# xmos1.net
KiCad netlist of a schematic drawn in EAGLE
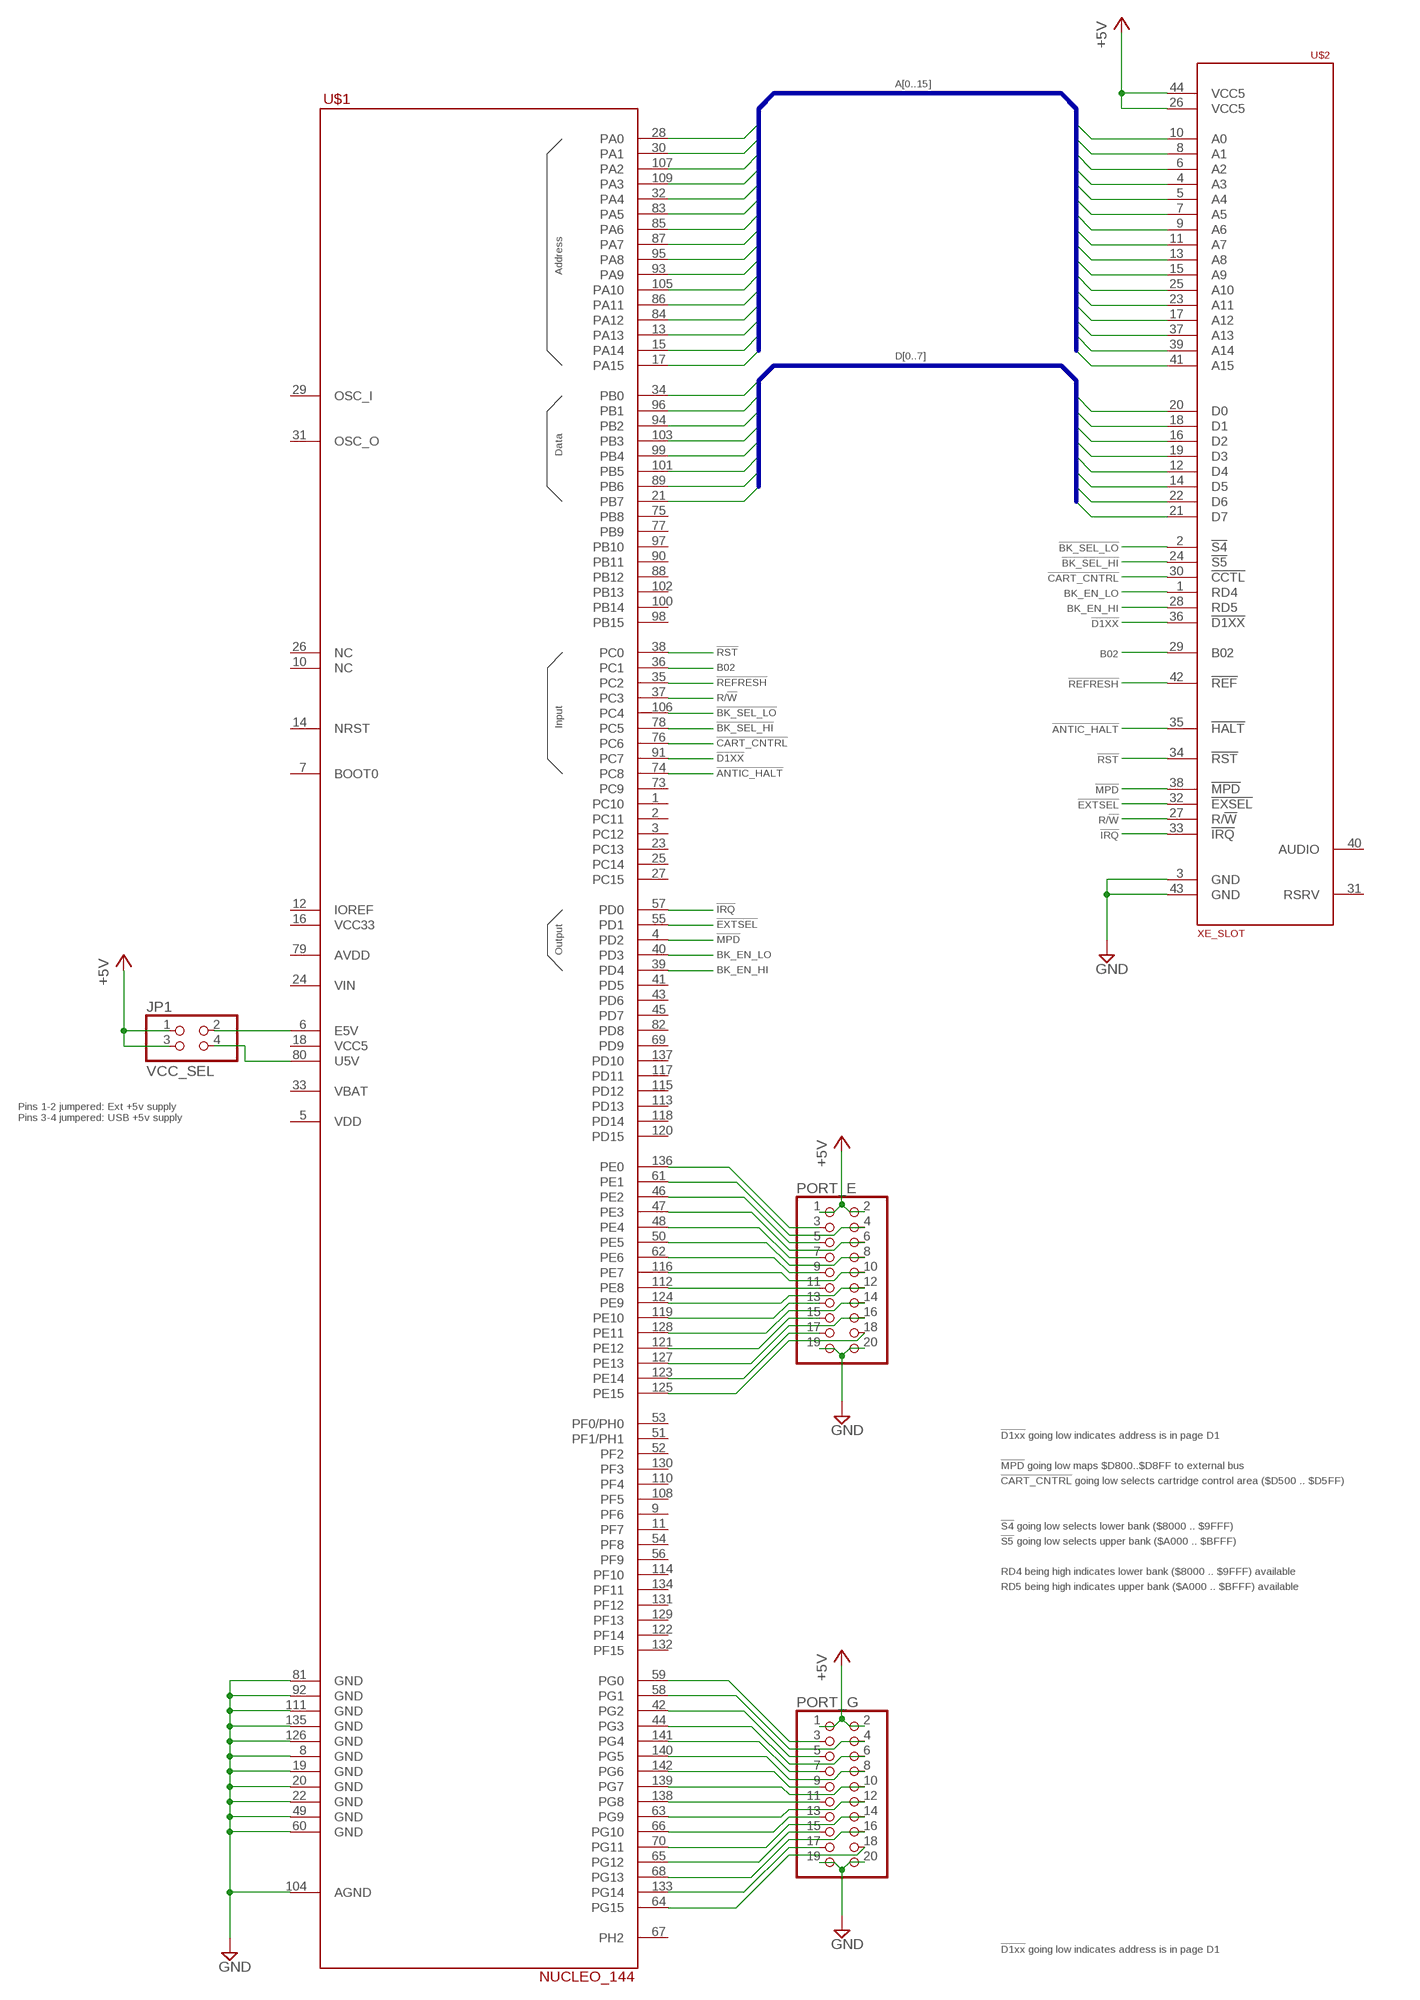
[diagram p0: schematic, sheet 1]

(export (version "E")
  (design (tool "Eeschema 10.0.6"))
  (components
    (comp (ref "JP1")
      (value "VCC_SEL")
      (footprint "eagle-import:2X02")
      (libsource (lib "eagle-import") (part "PINHD-2X2"))
    )
    (comp (ref "PORT_E")
      (value "PINHD-2X10")
      (footprint "eagle-import:2X10")
      (libsource (lib "eagle-import") (part "PINHD-2X10"))
    )
    (comp (ref "PORT_G")
      (value "PINHD-2X10")
      (footprint "eagle-import:2X10")
      (libsource (lib "eagle-import") (part "PINHD-2X10"))
    )
    (comp (ref "U$1")
      (value "NUCLEO_144")
      (footprint "eagle-import:NUCLEO_144")
      (libsource (lib "eagle-import") (part "NUCLEO_144"))
    )
    (comp (ref "U$2")
      (value "XE_SLOT")
      (footprint "eagle-import:XE_SLOT")
      (libsource (lib "eagle-import") (part "XE_SLOT"))
    )
  )
  (nets
    (net (code "1") (name "+5V") (class "Default")
      (node (ref "JP1") (pin "1") (pinfunction "1_1") (pintype "passive"))
      (node (ref "JP1") (pin "3") (pinfunction "3_3") (pintype "passive"))
      (node (ref "PORT_E") (pin "1") (pinfunction "1_1") (pintype "passive"))
      (node (ref "PORT_E") (pin "2") (pinfunction "2_2") (pintype "passive"))
      (node (ref "PORT_G") (pin "1") (pinfunction "1_1") (pintype "passive"))
      (node (ref "PORT_G") (pin "2") (pinfunction "2_2") (pintype "passive"))
      (node (ref "U$2") (pin "26") (pinfunction "VCC5_26") (pintype "bidirectional"))
      (node (ref "U$2") (pin "44") (pinfunction "VCC5_44") (pintype "bidirectional"))
    )
    (net (code "2") (name "/A0") (class "Default")
      (node (ref "U$1") (pin "28") (pinfunction "PA0_28") (pintype "bidirectional"))
      (node (ref "U$2") (pin "10") (pinfunction "A0_10") (pintype "bidirectional"))
    )
    (net (code "3") (name "/A1") (class "Default")
      (node (ref "U$1") (pin "30") (pinfunction "PA1_30") (pintype "bidirectional"))
      (node (ref "U$2") (pin "8") (pinfunction "A1_8") (pintype "bidirectional"))
    )
    (net (code "4") (name "/A2") (class "Default")
      (node (ref "U$1") (pin "107") (pinfunction "PA2_107") (pintype "bidirectional"))
      (node (ref "U$2") (pin "6") (pinfunction "A2_6") (pintype "bidirectional"))
    )
    (net (code "5") (name "/A3") (class "Default")
      (node (ref "U$1") (pin "109") (pinfunction "PA3_109") (pintype "bidirectional"))
      (node (ref "U$2") (pin "4") (pinfunction "A3_4") (pintype "bidirectional"))
    )
    (net (code "6") (name "/A4") (class "Default")
      (node (ref "U$1") (pin "32") (pinfunction "PA4_32") (pintype "bidirectional"))
      (node (ref "U$2") (pin "5") (pinfunction "A4_5") (pintype "bidirectional"))
    )
    (net (code "7") (name "/A5") (class "Default")
      (node (ref "U$1") (pin "83") (pinfunction "PA5_83") (pintype "bidirectional"))
      (node (ref "U$2") (pin "7") (pinfunction "A5_7") (pintype "bidirectional"))
    )
    (net (code "8") (name "/A6") (class "Default")
      (node (ref "U$1") (pin "85") (pinfunction "PA6_85") (pintype "bidirectional"))
      (node (ref "U$2") (pin "9") (pinfunction "A6_9") (pintype "bidirectional"))
    )
    (net (code "9") (name "/A7") (class "Default")
      (node (ref "U$1") (pin "87") (pinfunction "PA7_87") (pintype "bidirectional"))
      (node (ref "U$2") (pin "11") (pinfunction "A7_11") (pintype "bidirectional"))
    )
    (net (code "10") (name "/A8") (class "Default")
      (node (ref "U$1") (pin "95") (pinfunction "PA8_95") (pintype "bidirectional"))
      (node (ref "U$2") (pin "13") (pinfunction "A8_13") (pintype "bidirectional"))
    )
    (net (code "11") (name "/A9") (class "Default")
      (node (ref "U$1") (pin "93") (pinfunction "PA9_93") (pintype "bidirectional"))
      (node (ref "U$2") (pin "15") (pinfunction "A9_15") (pintype "bidirectional"))
    )
    (net (code "12") (name "/A10") (class "Default")
      (node (ref "U$1") (pin "105") (pinfunction "PA10_105") (pintype "bidirectional"))
      (node (ref "U$2") (pin "25") (pinfunction "A10_25") (pintype "bidirectional"))
    )
    (net (code "13") (name "/A11") (class "Default")
      (node (ref "U$1") (pin "86") (pinfunction "PA11_86") (pintype "bidirectional"))
      (node (ref "U$2") (pin "23") (pinfunction "A11_23") (pintype "bidirectional"))
    )
    (net (code "14") (name "/A12") (class "Default")
      (node (ref "U$1") (pin "84") (pinfunction "PA12_84") (pintype "bidirectional"))
      (node (ref "U$2") (pin "17") (pinfunction "A12_17") (pintype "bidirectional"))
    )
    (net (code "15") (name "/A13") (class "Default")
      (node (ref "U$1") (pin "13") (pinfunction "PA13_13") (pintype "bidirectional"))
      (node (ref "U$2") (pin "37") (pinfunction "A13_37") (pintype "bidirectional"))
    )
    (net (code "16") (name "/A14") (class "Default")
      (node (ref "U$1") (pin "15") (pinfunction "PA14_15") (pintype "bidirectional"))
      (node (ref "U$2") (pin "39") (pinfunction "A14_39") (pintype "bidirectional"))
    )
    (net (code "17") (name "/A15") (class "Default")
      (node (ref "U$1") (pin "17") (pinfunction "PA15_17") (pintype "bidirectional"))
      (node (ref "U$2") (pin "41") (pinfunction "A15_41") (pintype "bidirectional"))
    )
    (net (code "19") (name "/B02") (class "Default")
      (node (ref "U$1") (pin "36") (pinfunction "PC1_36") (pintype "bidirectional"))
      (node (ref "U$2") (pin "29") (pinfunction "B02_29") (pintype "bidirectional"))
    )
    (net (code "20") (name "/BK_EN_HI") (class "Default")
      (node (ref "U$1") (pin "39") (pinfunction "PD4_39") (pintype "bidirectional"))
      (node (ref "U$2") (pin "28") (pinfunction "RD5_28") (pintype "bidirectional"))
    )
    (net (code "21") (name "/BK_EN_LO") (class "Default")
      (node (ref "U$1") (pin "40") (pinfunction "PD3_40") (pintype "bidirectional"))
      (node (ref "U$2") (pin "1") (pinfunction "RD4_1") (pintype "bidirectional"))
    )
    (net (code "22") (name "/D0") (class "Default")
      (node (ref "U$1") (pin "34") (pinfunction "PB0_34") (pintype "bidirectional"))
      (node (ref "U$2") (pin "20") (pinfunction "D0_20") (pintype "bidirectional"))
    )
    (net (code "23") (name "/D1") (class "Default")
      (node (ref "U$1") (pin "96") (pinfunction "PB1_96") (pintype "bidirectional"))
      (node (ref "U$2") (pin "18") (pinfunction "D1_18") (pintype "bidirectional"))
    )
    (net (code "24") (name "/D2") (class "Default")
      (node (ref "U$1") (pin "94") (pinfunction "PB2_94") (pintype "bidirectional"))
      (node (ref "U$2") (pin "16") (pinfunction "D2_16") (pintype "bidirectional"))
    )
    (net (code "25") (name "/D3") (class "Default")
      (node (ref "U$1") (pin "103") (pinfunction "PB3_103") (pintype "bidirectional"))
      (node (ref "U$2") (pin "19") (pinfunction "D3_19") (pintype "bidirectional"))
    )
    (net (code "26") (name "/D4") (class "Default")
      (node (ref "U$1") (pin "99") (pinfunction "PB4_99") (pintype "bidirectional"))
      (node (ref "U$2") (pin "12") (pinfunction "D4_12") (pintype "bidirectional"))
    )
    (net (code "27") (name "/D5") (class "Default")
      (node (ref "U$1") (pin "101") (pinfunction "PB5_101") (pintype "bidirectional"))
      (node (ref "U$2") (pin "14") (pinfunction "D5_14") (pintype "bidirectional"))
    )
    (net (code "28") (name "/D6") (class "Default")
      (node (ref "U$1") (pin "89") (pinfunction "PB6_89") (pintype "bidirectional"))
      (node (ref "U$2") (pin "22") (pinfunction "D6_22") (pintype "bidirectional"))
    )
    (net (code "29") (name "/D7") (class "Default")
      (node (ref "U$1") (pin "21") (pinfunction "PB7_21") (pintype "bidirectional"))
      (node (ref "U$2") (pin "21") (pinfunction "D7_21") (pintype "bidirectional"))
    )
    (net (code "31") (name "/R{slash}~{W}") (class "Default")
      (node (ref "U$1") (pin "37") (pinfunction "PC3_37") (pintype "bidirectional"))
      (node (ref "U$2") (pin "27") (pinfunction "R/~{W}_27") (pintype "bidirectional"))
    )
    (net (code "32") (name "/~{ANTIC_HALT}") (class "Default")
      (node (ref "U$1") (pin "74") (pinfunction "PC8_74") (pintype "bidirectional"))
      (node (ref "U$2") (pin "35") (pinfunction "~{HALT}_35") (pintype "bidirectional"))
    )
    (net (code "33") (name "/~{BK_SEL_HI}") (class "Default")
      (node (ref "U$1") (pin "78") (pinfunction "PC5_78") (pintype "bidirectional"))
      (node (ref "U$2") (pin "24") (pinfunction "~{S5}_24") (pintype "bidirectional"))
    )
    (net (code "34") (name "/~{BK_SEL_LO}") (class "Default")
      (node (ref "U$1") (pin "106") (pinfunction "PC4_106") (pintype "bidirectional"))
      (node (ref "U$2") (pin "2") (pinfunction "~{S4}_2") (pintype "bidirectional"))
    )
    (net (code "35") (name "/~{CART_CNTRL}") (class "Default")
      (node (ref "U$1") (pin "76") (pinfunction "PC6_76") (pintype "bidirectional"))
      (node (ref "U$2") (pin "30") (pinfunction "~{CCTL}_30") (pintype "bidirectional"))
    )
    (net (code "36") (name "/~{D1XX}") (class "Default")
      (node (ref "U$1") (pin "91") (pinfunction "PC7_91") (pintype "bidirectional"))
      (node (ref "U$2") (pin "36") (pinfunction "~{D1XX}_36") (pintype "bidirectional"))
    )
    (net (code "37") (name "/~{EXTSEL}") (class "Default")
      (node (ref "U$1") (pin "55") (pinfunction "PD1_55") (pintype "bidirectional"))
      (node (ref "U$2") (pin "32") (pinfunction "~{EXSEL}_32") (pintype "bidirectional"))
    )
    (net (code "38") (name "/~{IRQ}") (class "Default")
      (node (ref "U$1") (pin "57") (pinfunction "PD0_57") (pintype "bidirectional"))
      (node (ref "U$2") (pin "33") (pinfunction "~{IRQ}_33") (pintype "bidirectional"))
    )
    (net (code "39") (name "/~{MPD}") (class "Default")
      (node (ref "U$1") (pin "4") (pinfunction "PD2_4") (pintype "bidirectional"))
      (node (ref "U$2") (pin "38") (pinfunction "~{MPD}_38") (pintype "bidirectional"))
    )
    (net (code "40") (name "/~{REFRESH}") (class "Default")
      (node (ref "U$1") (pin "35") (pinfunction "PC2_35") (pintype "bidirectional"))
      (node (ref "U$2") (pin "42") (pinfunction "~{REF}_42") (pintype "bidirectional"))
    )
    (net (code "41") (name "/~{RST}") (class "Default")
      (node (ref "U$1") (pin "38") (pinfunction "PC0_38") (pintype "bidirectional"))
      (node (ref "U$2") (pin "34") (pinfunction "~{RST}_34") (pintype "bidirectional"))
    )
    (net (code "42") (name "GND") (class "Default")
      (node (ref "PORT_E") (pin "19") (pinfunction "19_19") (pintype "passive"))
      (node (ref "PORT_E") (pin "20") (pinfunction "20_20") (pintype "passive"))
      (node (ref "PORT_G") (pin "19") (pinfunction "19_19") (pintype "passive"))
      (node (ref "PORT_G") (pin "20") (pinfunction "20_20") (pintype "passive"))
      (node (ref "U$1") (pin "104") (pinfunction "AGND_104") (pintype "bidirectional"))
      (node (ref "U$1") (pin "111") (pinfunction "GND_111") (pintype "bidirectional"))
      (node (ref "U$1") (pin "126") (pinfunction "GND_126") (pintype "bidirectional"))
      (node (ref "U$1") (pin "135") (pinfunction "GND_135") (pintype "bidirectional"))
      (node (ref "U$1") (pin "19") (pinfunction "GND_19") (pintype "bidirectional"))
      (node (ref "U$1") (pin "20") (pinfunction "GND_20") (pintype "bidirectional"))
      (node (ref "U$1") (pin "22") (pinfunction "GND_22") (pintype "bidirectional"))
      (node (ref "U$1") (pin "49") (pinfunction "GND_49") (pintype "bidirectional"))
      (node (ref "U$1") (pin "60") (pinfunction "GND_60") (pintype "bidirectional"))
      (node (ref "U$1") (pin "8") (pinfunction "GND_8") (pintype "bidirectional"))
      (node (ref "U$1") (pin "81") (pinfunction "GND_81") (pintype "bidirectional"))
      (node (ref "U$1") (pin "92") (pinfunction "GND_92") (pintype "bidirectional"))
      (node (ref "U$2") (pin "3") (pinfunction "GND_3") (pintype "bidirectional"))
      (node (ref "U$2") (pin "43") (pinfunction "GND_43") (pintype "bidirectional"))
    )
    (net (code "43") (name "Net-(U$1-E5V)") (class "Default")
      (node (ref "JP1") (pin "2") (pinfunction "2_2") (pintype "passive"))
      (node (ref "U$1") (pin "6") (pinfunction "E5V_6") (pintype "bidirectional"))
    )
    (net (code "44") (name "Net-(U$1-PE0)") (class "Default")
      (node (ref "PORT_E") (pin "3") (pinfunction "3_3") (pintype "passive"))
      (node (ref "U$1") (pin "136") (pinfunction "PE0_136") (pintype "bidirectional"))
    )
    (net (code "45") (name "Net-(U$1-PE1)") (class "Default")
      (node (ref "PORT_E") (pin "4") (pinfunction "4_4") (pintype "passive"))
      (node (ref "U$1") (pin "61") (pinfunction "PE1_61") (pintype "bidirectional"))
    )
    (net (code "46") (name "Net-(U$1-PE2)") (class "Default")
      (node (ref "PORT_E") (pin "5") (pinfunction "5_5") (pintype "passive"))
      (node (ref "U$1") (pin "46") (pinfunction "PE2_46") (pintype "bidirectional"))
    )
    (net (code "47") (name "Net-(U$1-PE3)") (class "Default")
      (node (ref "PORT_E") (pin "6") (pinfunction "6_6") (pintype "passive"))
      (node (ref "U$1") (pin "47") (pinfunction "PE3_47") (pintype "bidirectional"))
    )
    (net (code "48") (name "Net-(U$1-PE4)") (class "Default")
      (node (ref "PORT_E") (pin "7") (pinfunction "7_7") (pintype "passive"))
      (node (ref "U$1") (pin "48") (pinfunction "PE4_48") (pintype "bidirectional"))
    )
    (net (code "49") (name "Net-(U$1-PE5)") (class "Default")
      (node (ref "PORT_E") (pin "8") (pinfunction "8_8") (pintype "passive"))
      (node (ref "U$1") (pin "50") (pinfunction "PE5_50") (pintype "bidirectional"))
    )
    (net (code "50") (name "Net-(U$1-PE6)") (class "Default")
      (node (ref "PORT_E") (pin "9") (pinfunction "9_9") (pintype "passive"))
      (node (ref "U$1") (pin "62") (pinfunction "PE6_62") (pintype "bidirectional"))
    )
    (net (code "51") (name "Net-(U$1-PE7)") (class "Default")
      (node (ref "PORT_E") (pin "10") (pinfunction "10_10") (pintype "passive"))
      (node (ref "U$1") (pin "116") (pinfunction "PE7_116") (pintype "bidirectional"))
    )
    (net (code "52") (name "Net-(U$1-PE8)") (class "Default")
      (node (ref "PORT_E") (pin "11") (pinfunction "11_11") (pintype "passive"))
      (node (ref "U$1") (pin "112") (pinfunction "PE8_112") (pintype "bidirectional"))
    )
    (net (code "53") (name "Net-(U$1-PE9)") (class "Default")
      (node (ref "PORT_E") (pin "12") (pinfunction "12_12") (pintype "passive"))
      (node (ref "U$1") (pin "124") (pinfunction "PE9_124") (pintype "bidirectional"))
    )
    (net (code "54") (name "Net-(U$1-PE10)") (class "Default")
      (node (ref "PORT_E") (pin "13") (pinfunction "13_13") (pintype "passive"))
      (node (ref "U$1") (pin "119") (pinfunction "PE10_119") (pintype "bidirectional"))
    )
    (net (code "55") (name "Net-(U$1-PE11)") (class "Default")
      (node (ref "PORT_E") (pin "14") (pinfunction "14_14") (pintype "passive"))
      (node (ref "U$1") (pin "128") (pinfunction "PE11_128") (pintype "bidirectional"))
    )
    (net (code "56") (name "Net-(U$1-PE12)") (class "Default")
      (node (ref "PORT_E") (pin "15") (pinfunction "15_15") (pintype "passive"))
      (node (ref "U$1") (pin "121") (pinfunction "PE12_121") (pintype "bidirectional"))
    )
    (net (code "57") (name "Net-(U$1-PE13)") (class "Default")
      (node (ref "PORT_E") (pin "16") (pinfunction "16_16") (pintype "passive"))
      (node (ref "U$1") (pin "127") (pinfunction "PE13_127") (pintype "bidirectional"))
    )
    (net (code "58") (name "Net-(U$1-PE14)") (class "Default")
      (node (ref "PORT_E") (pin "17") (pinfunction "17_17") (pintype "passive"))
      (node (ref "U$1") (pin "123") (pinfunction "PE14_123") (pintype "bidirectional"))
    )
    (net (code "59") (name "Net-(U$1-PE15)") (class "Default")
      (node (ref "PORT_E") (pin "18") (pinfunction "18_18") (pintype "passive"))
      (node (ref "U$1") (pin "125") (pinfunction "PE15_125") (pintype "bidirectional"))
    )
    (net (code "60") (name "Net-(U$1-PG0)") (class "Default")
      (node (ref "PORT_G") (pin "3") (pinfunction "3_3") (pintype "passive"))
      (node (ref "U$1") (pin "59") (pinfunction "PG0_59") (pintype "bidirectional"))
    )
    (net (code "61") (name "Net-(U$1-PG1)") (class "Default")
      (node (ref "PORT_G") (pin "4") (pinfunction "4_4") (pintype "passive"))
      (node (ref "U$1") (pin "58") (pinfunction "PG1_58") (pintype "bidirectional"))
    )
    (net (code "62") (name "Net-(U$1-PG2)") (class "Default")
      (node (ref "PORT_G") (pin "5") (pinfunction "5_5") (pintype "passive"))
      (node (ref "U$1") (pin "42") (pinfunction "PG2_42") (pintype "bidirectional"))
    )
    (net (code "63") (name "Net-(U$1-PG3)") (class "Default")
      (node (ref "PORT_G") (pin "6") (pinfunction "6_6") (pintype "passive"))
      (node (ref "U$1") (pin "44") (pinfunction "PG3_44") (pintype "bidirectional"))
    )
    (net (code "64") (name "Net-(U$1-PG4)") (class "Default")
      (node (ref "PORT_G") (pin "7") (pinfunction "7_7") (pintype "passive"))
      (node (ref "U$1") (pin "141") (pinfunction "PG4_141") (pintype "bidirectional"))
    )
    (net (code "65") (name "Net-(U$1-PG5)") (class "Default")
      (node (ref "PORT_G") (pin "8") (pinfunction "8_8") (pintype "passive"))
      (node (ref "U$1") (pin "140") (pinfunction "PG5_140") (pintype "bidirectional"))
    )
    (net (code "66") (name "Net-(U$1-PG6)") (class "Default")
      (node (ref "PORT_G") (pin "9") (pinfunction "9_9") (pintype "passive"))
      (node (ref "U$1") (pin "142") (pinfunction "PG6_142") (pintype "bidirectional"))
    )
    (net (code "67") (name "Net-(U$1-PG7)") (class "Default")
      (node (ref "PORT_G") (pin "10") (pinfunction "10_10") (pintype "passive"))
      (node (ref "U$1") (pin "139") (pinfunction "PG7_139") (pintype "bidirectional"))
    )
    (net (code "68") (name "Net-(U$1-PG8)") (class "Default")
      (node (ref "PORT_G") (pin "11") (pinfunction "11_11") (pintype "passive"))
      (node (ref "U$1") (pin "138") (pinfunction "PG8_138") (pintype "bidirectional"))
    )
    (net (code "69") (name "Net-(U$1-PG9)") (class "Default")
      (node (ref "PORT_G") (pin "12") (pinfunction "12_12") (pintype "passive"))
      (node (ref "U$1") (pin "63") (pinfunction "PG9_63") (pintype "bidirectional"))
    )
    (net (code "70") (name "Net-(U$1-PG10)") (class "Default")
      (node (ref "PORT_G") (pin "13") (pinfunction "13_13") (pintype "passive"))
      (node (ref "U$1") (pin "66") (pinfunction "PG10_66") (pintype "bidirectional"))
    )
    (net (code "71") (name "Net-(U$1-PG11)") (class "Default")
      (node (ref "PORT_G") (pin "14") (pinfunction "14_14") (pintype "passive"))
      (node (ref "U$1") (pin "70") (pinfunction "PG11_70") (pintype "bidirectional"))
    )
    (net (code "72") (name "Net-(U$1-PG12)") (class "Default")
      (node (ref "PORT_G") (pin "15") (pinfunction "15_15") (pintype "passive"))
      (node (ref "U$1") (pin "65") (pinfunction "PG12_65") (pintype "bidirectional"))
    )
    (net (code "73") (name "Net-(U$1-PG13)") (class "Default")
      (node (ref "PORT_G") (pin "16") (pinfunction "16_16") (pintype "passive"))
      (node (ref "U$1") (pin "68") (pinfunction "PG13_68") (pintype "bidirectional"))
    )
    (net (code "74") (name "Net-(U$1-PG14)") (class "Default")
      (node (ref "PORT_G") (pin "17") (pinfunction "17_17") (pintype "passive"))
      (node (ref "U$1") (pin "133") (pinfunction "PG14_133") (pintype "bidirectional"))
    )
    (net (code "75") (name "Net-(U$1-PG15)") (class "Default")
      (node (ref "PORT_G") (pin "18") (pinfunction "18_18") (pintype "passive"))
      (node (ref "U$1") (pin "64") (pinfunction "PG15_64") (pintype "bidirectional"))
    )
    (net (code "76") (name "Net-(U$1-U5V)") (class "Default")
      (node (ref "JP1") (pin "4") (pinfunction "4_4") (pintype "passive"))
      (node (ref "U$1") (pin "80") (pinfunction "U5V_80") (pintype "bidirectional"))
    )
    (net (code "77") (name "unconnected-(U$1-AVDD-Pad79)") (class "Default")
      (node (ref "U$1") (pin "79") (pinfunction "AVDD_79") (pintype "bidirectional"))
    )
    (net (code "78") (name "unconnected-(U$1-BOOT0-Pad7)") (class "Default")
      (node (ref "U$1") (pin "7") (pinfunction "BOOT0_7") (pintype "bidirectional"))
    )
    (net (code "79") (name "unconnected-(U$1-IOREF-Pad12)") (class "Default")
      (node (ref "U$1") (pin "12") (pinfunction "IOREF_12") (pintype "bidirectional"))
    )
    (net (code "80") (name "unconnected-(U$1-NC-Pad10)") (class "Default")
      (node (ref "U$1") (pin "10") (pinfunction "NC_10") (pintype "bidirectional"))
    )
    (net (code "81") (name "unconnected-(U$1-NC-Pad26)") (class "Default")
      (node (ref "U$1") (pin "26") (pinfunction "NC_26") (pintype "bidirectional"))
    )
    (net (code "82") (name "unconnected-(U$1-NRST-Pad14)") (class "Default")
      (node (ref "U$1") (pin "14") (pinfunction "NRST_14") (pintype "bidirectional"))
    )
    (net (code "83") (name "unconnected-(U$1-OSC_I-Pad29)") (class "Default")
      (node (ref "U$1") (pin "29") (pinfunction "OSC_I_29") (pintype "bidirectional"))
    )
    (net (code "84") (name "unconnected-(U$1-OSC_O-Pad31)") (class "Default")
      (node (ref "U$1") (pin "31") (pinfunction "OSC_O_31") (pintype "bidirectional"))
    )
    (net (code "85") (name "unconnected-(U$1-PB8-Pad75)") (class "Default")
      (node (ref "U$1") (pin "75") (pinfunction "PB8_75") (pintype "bidirectional"))
    )
    (net (code "86") (name "unconnected-(U$1-PB9-Pad77)") (class "Default")
      (node (ref "U$1") (pin "77") (pinfunction "PB9_77") (pintype "bidirectional"))
    )
    (net (code "87") (name "unconnected-(U$1-PB10-Pad97)") (class "Default")
      (node (ref "U$1") (pin "97") (pinfunction "PB10_97") (pintype "bidirectional"))
    )
    (net (code "88") (name "unconnected-(U$1-PB11-Pad90)") (class "Default")
      (node (ref "U$1") (pin "90") (pinfunction "PB11_90") (pintype "bidirectional"))
    )
    (net (code "89") (name "unconnected-(U$1-PB12-Pad88)") (class "Default")
      (node (ref "U$1") (pin "88") (pinfunction "PB12_88") (pintype "bidirectional"))
    )
    (net (code "90") (name "unconnected-(U$1-PB13-Pad102)") (class "Default")
      (node (ref "U$1") (pin "102") (pinfunction "PB13_102") (pintype "bidirectional"))
    )
    (net (code "91") (name "unconnected-(U$1-PB14-Pad100)") (class "Default")
      (node (ref "U$1") (pin "100") (pinfunction "PB14_100") (pintype "bidirectional"))
    )
    (net (code "92") (name "unconnected-(U$1-PB15-Pad98)") (class "Default")
      (node (ref "U$1") (pin "98") (pinfunction "PB15_98") (pintype "bidirectional"))
    )
    (net (code "93") (name "unconnected-(U$1-PC9-Pad73)") (class "Default")
      (node (ref "U$1") (pin "73") (pinfunction "PC9_73") (pintype "bidirectional"))
    )
    (net (code "94") (name "unconnected-(U$1-PC10-Pad1)") (class "Default")
      (node (ref "U$1") (pin "1") (pinfunction "PC10_1") (pintype "bidirectional"))
    )
    (net (code "95") (name "unconnected-(U$1-PC11-Pad2)") (class "Default")
      (node (ref "U$1") (pin "2") (pinfunction "PC11_2") (pintype "bidirectional"))
    )
    (net (code "96") (name "unconnected-(U$1-PC12-Pad3)") (class "Default")
      (node (ref "U$1") (pin "3") (pinfunction "PC12_3") (pintype "bidirectional"))
    )
    (net (code "97") (name "unconnected-(U$1-PC13-Pad23)") (class "Default")
      (node (ref "U$1") (pin "23") (pinfunction "PC13_23") (pintype "bidirectional"))
    )
    (net (code "98") (name "unconnected-(U$1-PC14-Pad25)") (class "Default")
      (node (ref "U$1") (pin "25") (pinfunction "PC14_25") (pintype "bidirectional"))
    )
    (net (code "99") (name "unconnected-(U$1-PC15-Pad27)") (class "Default")
      (node (ref "U$1") (pin "27") (pinfunction "PC15_27") (pintype "bidirectional"))
    )
    (net (code "100") (name "unconnected-(U$1-PD5-Pad41)") (class "Default")
      (node (ref "U$1") (pin "41") (pinfunction "PD5_41") (pintype "bidirectional"))
    )
    (net (code "101") (name "unconnected-(U$1-PD6-Pad43)") (class "Default")
      (node (ref "U$1") (pin "43") (pinfunction "PD6_43") (pintype "bidirectional"))
    )
    (net (code "102") (name "unconnected-(U$1-PD7-Pad45)") (class "Default")
      (node (ref "U$1") (pin "45") (pinfunction "PD7_45") (pintype "bidirectional"))
    )
    (net (code "103") (name "unconnected-(U$1-PD8-Pad82)") (class "Default")
      (node (ref "U$1") (pin "82") (pinfunction "PD8_82") (pintype "bidirectional"))
    )
    (net (code "104") (name "unconnected-(U$1-PD9-Pad69)") (class "Default")
      (node (ref "U$1") (pin "69") (pinfunction "PD9_69") (pintype "bidirectional"))
    )
    (net (code "105") (name "unconnected-(U$1-PD10-Pad137)") (class "Default")
      (node (ref "U$1") (pin "137") (pinfunction "PD10_137") (pintype "bidirectional"))
    )
    (net (code "106") (name "unconnected-(U$1-PD11-Pad117)") (class "Default")
      (node (ref "U$1") (pin "117") (pinfunction "PD11_117") (pintype "bidirectional"))
    )
    (net (code "107") (name "unconnected-(U$1-PD12-Pad115)") (class "Default")
      (node (ref "U$1") (pin "115") (pinfunction "PD12_115") (pintype "bidirectional"))
    )
    (net (code "108") (name "unconnected-(U$1-PD13-Pad113)") (class "Default")
      (node (ref "U$1") (pin "113") (pinfunction "PD13_113") (pintype "bidirectional"))
    )
    (net (code "109") (name "unconnected-(U$1-PD14-Pad118)") (class "Default")
      (node (ref "U$1") (pin "118") (pinfunction "PD14_118") (pintype "bidirectional"))
    )
    (net (code "110") (name "unconnected-(U$1-PD15-Pad120)") (class "Default")
      (node (ref "U$1") (pin "120") (pinfunction "PD15_120") (pintype "bidirectional"))
    )
    (net (code "111") (name "unconnected-(U$1-PF0{slash}PH0-Pad53)") (class "Default")
      (node (ref "U$1") (pin "53") (pinfunction "PF0/PH0_53") (pintype "bidirectional"))
    )
    (net (code "112") (name "unconnected-(U$1-PF1{slash}PH1-Pad51)") (class "Default")
      (node (ref "U$1") (pin "51") (pinfunction "PF1/PH1_51") (pintype "bidirectional"))
    )
    (net (code "113") (name "unconnected-(U$1-PF2-Pad52)") (class "Default")
      (node (ref "U$1") (pin "52") (pinfunction "PF2_52") (pintype "bidirectional"))
    )
    (net (code "114") (name "unconnected-(U$1-PF3-Pad130)") (class "Default")
      (node (ref "U$1") (pin "130") (pinfunction "PF3_130") (pintype "bidirectional"))
    )
    (net (code "115") (name "unconnected-(U$1-PF4-Pad110)") (class "Default")
      (node (ref "U$1") (pin "110") (pinfunction "PF4_110") (pintype "bidirectional"))
    )
    (net (code "116") (name "unconnected-(U$1-PF5-Pad108)") (class "Default")
      (node (ref "U$1") (pin "108") (pinfunction "PF5_108") (pintype "bidirectional"))
    )
    (net (code "117") (name "unconnected-(U$1-PF6-Pad9)") (class "Default")
      (node (ref "U$1") (pin "9") (pinfunction "PF6_9") (pintype "bidirectional"))
    )
    (net (code "118") (name "unconnected-(U$1-PF7-Pad11)") (class "Default")
      (node (ref "U$1") (pin "11") (pinfunction "PF7_11") (pintype "bidirectional"))
    )
    (net (code "119") (name "unconnected-(U$1-PF8-Pad54)") (class "Default")
      (node (ref "U$1") (pin "54") (pinfunction "PF8_54") (pintype "bidirectional"))
    )
    (net (code "120") (name "unconnected-(U$1-PF9-Pad56)") (class "Default")
      (node (ref "U$1") (pin "56") (pinfunction "PF9_56") (pintype "bidirectional"))
    )
    (net (code "121") (name "unconnected-(U$1-PF10-Pad114)") (class "Default")
      (node (ref "U$1") (pin "114") (pinfunction "PF10_114") (pintype "bidirectional"))
    )
    (net (code "122") (name "unconnected-(U$1-PF11-Pad134)") (class "Default")
      (node (ref "U$1") (pin "134") (pinfunction "PF11_134") (pintype "bidirectional"))
    )
    (net (code "123") (name "unconnected-(U$1-PF12-Pad131)") (class "Default")
      (node (ref "U$1") (pin "131") (pinfunction "PF12_131") (pintype "bidirectional"))
    )
    (net (code "124") (name "unconnected-(U$1-PF13-Pad129)") (class "Default")
      (node (ref "U$1") (pin "129") (pinfunction "PF13_129") (pintype "bidirectional"))
    )
    (net (code "125") (name "unconnected-(U$1-PF14-Pad122)") (class "Default")
      (node (ref "U$1") (pin "122") (pinfunction "PF14_122") (pintype "bidirectional"))
    )
    (net (code "126") (name "unconnected-(U$1-PF15-Pad132)") (class "Default")
      (node (ref "U$1") (pin "132") (pinfunction "PF15_132") (pintype "bidirectional"))
    )
    (net (code "127") (name "unconnected-(U$1-PH2-Pad67)") (class "Default")
      (node (ref "U$1") (pin "67") (pinfunction "PH2_67") (pintype "bidirectional"))
    )
    (net (code "128") (name "unconnected-(U$1-VBAT-Pad33)") (class "Default")
      (node (ref "U$1") (pin "33") (pinfunction "VBAT_33") (pintype "bidirectional"))
    )
    (net (code "129") (name "unconnected-(U$1-VCC5-Pad18)") (class "Default")
      (node (ref "U$1") (pin "18") (pinfunction "VCC5_18") (pintype "bidirectional"))
    )
    (net (code "130") (name "unconnected-(U$1-VCC33-Pad16)") (class "Default")
      (node (ref "U$1") (pin "16") (pinfunction "VCC33_16") (pintype "bidirectional"))
    )
    (net (code "131") (name "unconnected-(U$1-VDD-Pad5)") (class "Default")
      (node (ref "U$1") (pin "5") (pinfunction "VDD_5") (pintype "bidirectional"))
    )
    (net (code "132") (name "unconnected-(U$1-VIN-Pad24)") (class "Default")
      (node (ref "U$1") (pin "24") (pinfunction "VIN_24") (pintype "bidirectional"))
    )
    (net (code "133") (name "unconnected-(U$2-AUDIO-Pad40)") (class "Default")
      (node (ref "U$2") (pin "40") (pinfunction "AUDIO_40") (pintype "bidirectional"))
    )
    (net (code "134") (name "unconnected-(U$2-RSRV-Pad31)") (class "Default")
      (node (ref "U$2") (pin "31") (pinfunction "RSRV_31") (pintype "bidirectional"))
    )
  )
)
